# FridgeWarninig_0_5.net
KiCad netlist of a schematic drawn in EAGLE
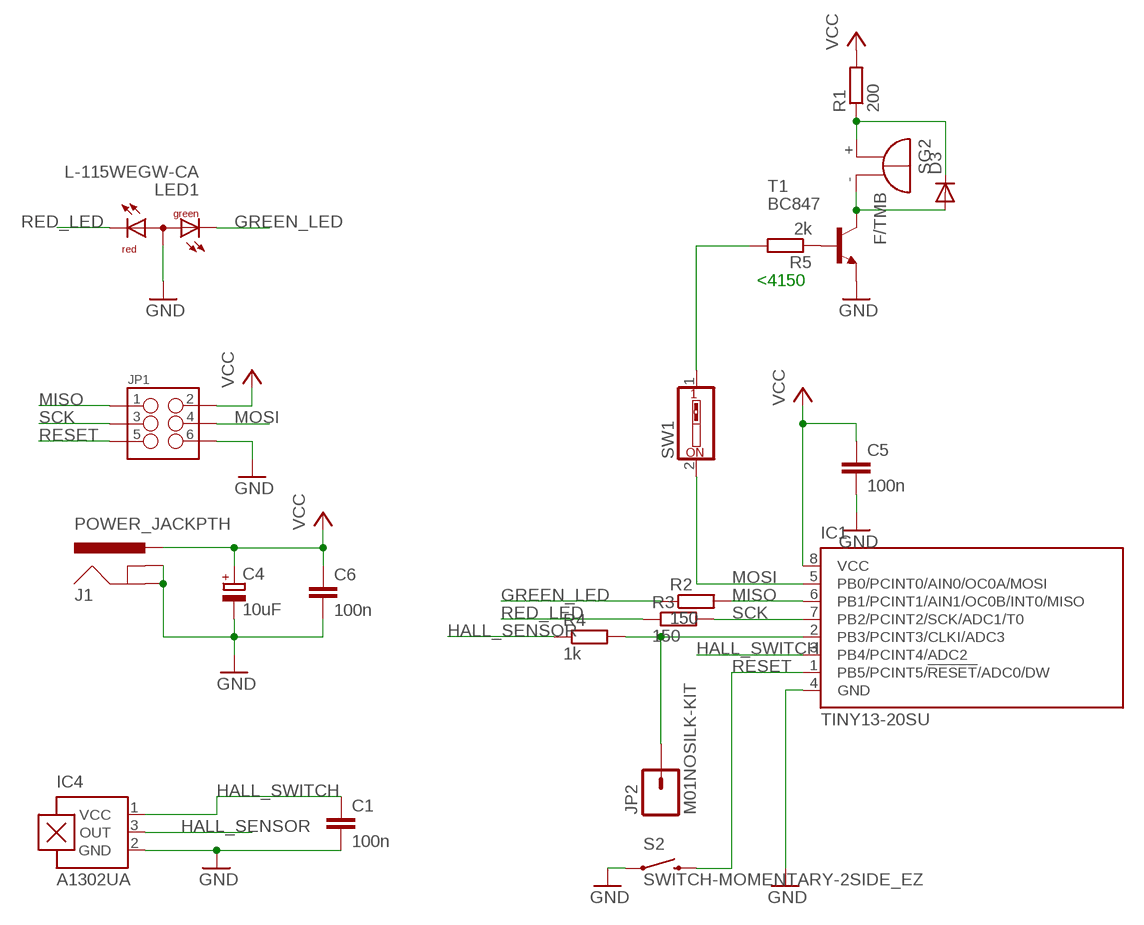
[diagram p0: schematic, sheet 1]

(export (version "E")
  (design (tool "Eeschema 10.0.6"))
  (components
    (comp (ref "C1")
      (value "100n")
      (footprint "eagle-import:C0603")
      (libsource (lib "eagle-import") (part "C-EUC0603"))
    )
    (comp (ref "C4")
      (value "10uF")
      (footprint "eagle-import:E2-5")
      (libsource (lib "eagle-import") (part "CPOL-EUE2-5"))
    )
    (comp (ref "C5")
      (value "100n")
      (footprint "eagle-import:C0603")
      (libsource (lib "eagle-import") (part "C-EUC0603"))
    )
    (comp (ref "C6")
      (value "100n")
      (footprint "eagle-import:C0603")
      (libsource (lib "eagle-import") (part "C-EUC0603"))
    )
    (comp (ref "D3")
      (value "DIODE-DO-214AC")
      (footprint "eagle-import:DO-214AC")
      (libsource (lib "eagle-import") (part "DIODE-DO-214AC"))
    )
    (comp (ref "IC1")
      (value "TINY13-20SU")
      (footprint "eagle-import:8S2")
      (fields (field (name "MPN") "ATTINY13-20SU"))
      (libsource (lib "eagle-import") (part "TINY13SU-20"))
    )
    (comp (ref "IC4")
      (value "A1302UA")
      (footprint "eagle-import:SIP3-UA")
      (fields (field (name "MF") "ALLEGRO MICROSYSTEMS, INC.") (field (name "MPN") "A1302EUA-T"))
      (libsource (lib "eagle-import") (part "A13?UA02"))
    )
    (comp (ref "J1")
      (value "POWER_JACKPTH")
      (footprint "eagle-import:POWER_JACK_PTH")
      (libsource (lib "eagle-import") (part "POWER_JACKPTH"))
    )
    (comp (ref "JP1")
      (value "M03X2SHROUD")
      (footprint "eagle-import:2X3-SHROUDED")
      (libsource (lib "eagle-import") (part "M03X2SHROUD"))
    )
    (comp (ref "JP2")
      (value "M01NOSILK-KIT")
      (footprint "eagle-import:1X01NS-KIT")
      (libsource (lib "eagle-import") (part "M01NOSILK-KIT"))
    )
    (comp (ref "LED1")
      (value "L-115WEGW-CA")
      (footprint "eagle-import:DUOLED-A-3MM")
      (libsource (lib "eagle-import") (part "L-115WEGW-CA"))
    )
    (comp (ref "R1")
      (value "200")
      (footprint "eagle-import:R0603")
      (libsource (lib "eagle-import") (part "R-EU_R0603"))
    )
    (comp (ref "R2")
      (value "150")
      (footprint "eagle-import:R0603")
      (libsource (lib "eagle-import") (part "R-EU_R0603"))
    )
    (comp (ref "R3")
      (value "150")
      (footprint "eagle-import:R0603")
      (libsource (lib "eagle-import") (part "R-EU_R0603"))
    )
    (comp (ref "R4")
      (value "1k")
      (footprint "eagle-import:R0603")
      (libsource (lib "eagle-import") (part "R-EU_R0603"))
    )
    (comp (ref "R5")
      (value "2k")
      (footprint "eagle-import:R0603")
      (libsource (lib "eagle-import") (part "R-EU_R0603"))
    )
    (comp (ref "S2")
      (value "SWITCH-MOMENTARY-2SIDE_EZ")
      (footprint "eagle-import:TACTILE-PTH-SIDEEZ")
      (libsource (lib "eagle-import") (part "SWITCH-MOMENTARY-2SIDE_EZ"))
    )
    (comp (ref "SG2")
      (value "F/TMB")
      (footprint "eagle-import:F_TMB")
      (libsource (lib "eagle-import") (part "F/TMB"))
    )
    (comp (ref "SW1")
      (value "SW_DIP-1")
      (footprint "eagle-import:EDG-01")
      (libsource (lib "eagle-import") (part "SW_DIP-1"))
    )
    (comp (ref "T1")
      (value "BC847")
      (footprint "eagle-import:SOT23")
      (libsource (lib "eagle-import") (part "BC847"))
    )
  )
  (nets
    (net (code "1") (name "/GREEN_LED") (class "Default")
      (node (ref "LED1") (pin "1") (pinfunction "CG_1") (pintype "passive"))
      (node (ref "R2") (pin "1") (pinfunction "1_1") (pintype "passive"))
    )
    (net (code "2") (name "/HALL_SENSOR") (class "Default")
      (node (ref "IC4") (pin "3") (pinfunction "OUT_3") (pintype "output"))
      (node (ref "R4") (pin "1") (pinfunction "1_1") (pintype "passive"))
    )
    (net (code "3") (name "/HALL_SWITCH") (class "Default")
      (node (ref "C1") (pin "1") (pinfunction "1_1") (pintype "passive"))
      (node (ref "IC1") (pin "3") (pinfunction "PB4/PCINT4/ADC2_3") (pintype "bidirectional"))
      (node (ref "IC4") (pin "1") (pinfunction "VCC_1") (pintype "power_in"))
    )
    (net (code "4") (name "/MISO") (class "Default")
      (node (ref "IC1") (pin "6") (pinfunction "PB1/PCINT1/AIN1/OC0B/INT0/MISO_6") (pintype "bidirectional"))
      (node (ref "JP1") (pin "1") (pinfunction "1_1") (pintype "bidirectional"))
      (node (ref "R2") (pin "2") (pinfunction "2_2") (pintype "passive"))
    )
    (net (code "5") (name "/MOSI") (class "Default")
      (node (ref "IC1") (pin "5") (pinfunction "PB0/PCINT0/AIN0/OC0A/MOSI_5") (pintype "bidirectional"))
      (node (ref "JP1") (pin "4") (pinfunction "4_4") (pintype "bidirectional"))
      (node (ref "SW1") (pin "2") (pinfunction "2_2") (pintype "passive"))
    )
    (net (code "6") (name "/RED_LED") (class "Default")
      (node (ref "LED1") (pin "3") (pinfunction "CR_3") (pintype "passive"))
      (node (ref "R3") (pin "1") (pinfunction "1_1") (pintype "passive"))
    )
    (net (code "7") (name "/RESET") (class "Default")
      (node (ref "IC1") (pin "1") (pinfunction "PB5/PCINT5/~{RESET}/ADC0/DW_1") (pintype "bidirectional"))
      (node (ref "JP1") (pin "5") (pinfunction "5_5") (pintype "bidirectional"))
      (node (ref "S2") (pin "2") (pinfunction "2_2") (pintype "passive"))
    )
    (net (code "8") (name "/SCK") (class "Default")
      (node (ref "IC1") (pin "7") (pinfunction "PB2/PCINT2/SCK/ADC1/T0_7") (pintype "bidirectional"))
      (node (ref "JP1") (pin "3") (pinfunction "3_3") (pintype "bidirectional"))
      (node (ref "R3") (pin "2") (pinfunction "2_2") (pintype "passive"))
    )
    (net (code "9") (name "GND") (class "Default")
      (node (ref "C1") (pin "2") (pinfunction "2_2") (pintype "passive"))
      (node (ref "C4") (pin "-") (pinfunction "-_-") (pintype "passive"))
      (node (ref "C5") (pin "2") (pinfunction "2_2") (pintype "passive"))
      (node (ref "C6") (pin "2") (pinfunction "2_2") (pintype "passive"))
      (node (ref "IC1") (pin "4") (pinfunction "GND_4") (pintype "power_in"))
      (node (ref "IC4") (pin "2") (pinfunction "GND_2") (pintype "power_in"))
      (node (ref "J1") (pin "GND") (pinfunction "GND_GND") (pintype "bidirectional"))
      (node (ref "J1") (pin "GNDBREAK") (pinfunction "GNDBREAK_GNDBREAK") (pintype "bidirectional"))
      (node (ref "JP1") (pin "6") (pinfunction "6_6") (pintype "bidirectional"))
      (node (ref "LED1") (pin "2") (pinfunction "A_2") (pintype "passive"))
      (node (ref "S2") (pin "1") (pinfunction "1_1") (pintype "passive"))
      (node (ref "T1") (pin "2") (pinfunction "E_2") (pintype "passive"))
    )
    (net (code "10") (name "Net-(D3-A)") (class "Default")
      (node (ref "D3") (pin "2") (pinfunction "A_2") (pintype "passive"))
      (node (ref "SG2") (pin "-") (pinfunction "-_-") (pintype "passive"))
      (node (ref "T1") (pin "3") (pinfunction "C_3") (pintype "passive"))
    )
    (net (code "11") (name "Net-(D3-C)") (class "Default")
      (node (ref "D3") (pin "1") (pinfunction "C_1") (pintype "passive"))
      (node (ref "R1") (pin "1") (pinfunction "1_1") (pintype "passive"))
      (node (ref "SG2") (pin "+") (pinfunction "+_+") (pintype "passive"))
    )
    (net (code "12") (name "Net-(IC1-PB3{slash}PCINT3{slash}CLKI{slash}ADC3)") (class "Default")
      (node (ref "IC1") (pin "2") (pinfunction "PB3/PCINT3/CLKI/ADC3_2") (pintype "bidirectional"))
      (node (ref "JP2") (pin "1") (pinfunction "1_1") (pintype "passive"))
      (node (ref "R4") (pin "2") (pinfunction "2_2") (pintype "passive"))
    )
    (net (code "13") (name "Net-(R5-Pad2)") (class "Default")
      (node (ref "R5") (pin "2") (pinfunction "2_2") (pintype "passive"))
      (node (ref "SW1") (pin "1") (pinfunction "1_1") (pintype "passive"))
    )
    (net (code "14") (name "Net-(T1-B)") (class "Default")
      (node (ref "R5") (pin "1") (pinfunction "1_1") (pintype "passive"))
      (node (ref "T1") (pin "1") (pinfunction "B_1") (pintype "passive"))
    )
    (net (code "15") (name "VCC") (class "Default")
      (node (ref "C4") (pin "+") (pinfunction "+_+") (pintype "passive"))
      (node (ref "C5") (pin "1") (pinfunction "1_1") (pintype "passive"))
      (node (ref "C6") (pin "1") (pinfunction "1_1") (pintype "passive"))
      (node (ref "IC1") (pin "8") (pinfunction "VCC_8") (pintype "power_in"))
      (node (ref "J1") (pin "PWR") (pinfunction "PWR_PWR") (pintype "bidirectional"))
      (node (ref "JP1") (pin "2") (pinfunction "2_2") (pintype "bidirectional"))
      (node (ref "R1") (pin "2") (pinfunction "2_2") (pintype "passive"))
    )
  )
)
